# BOTCPCB_IXYS.net
KiCad netlist of a schematic drawn in EAGLE
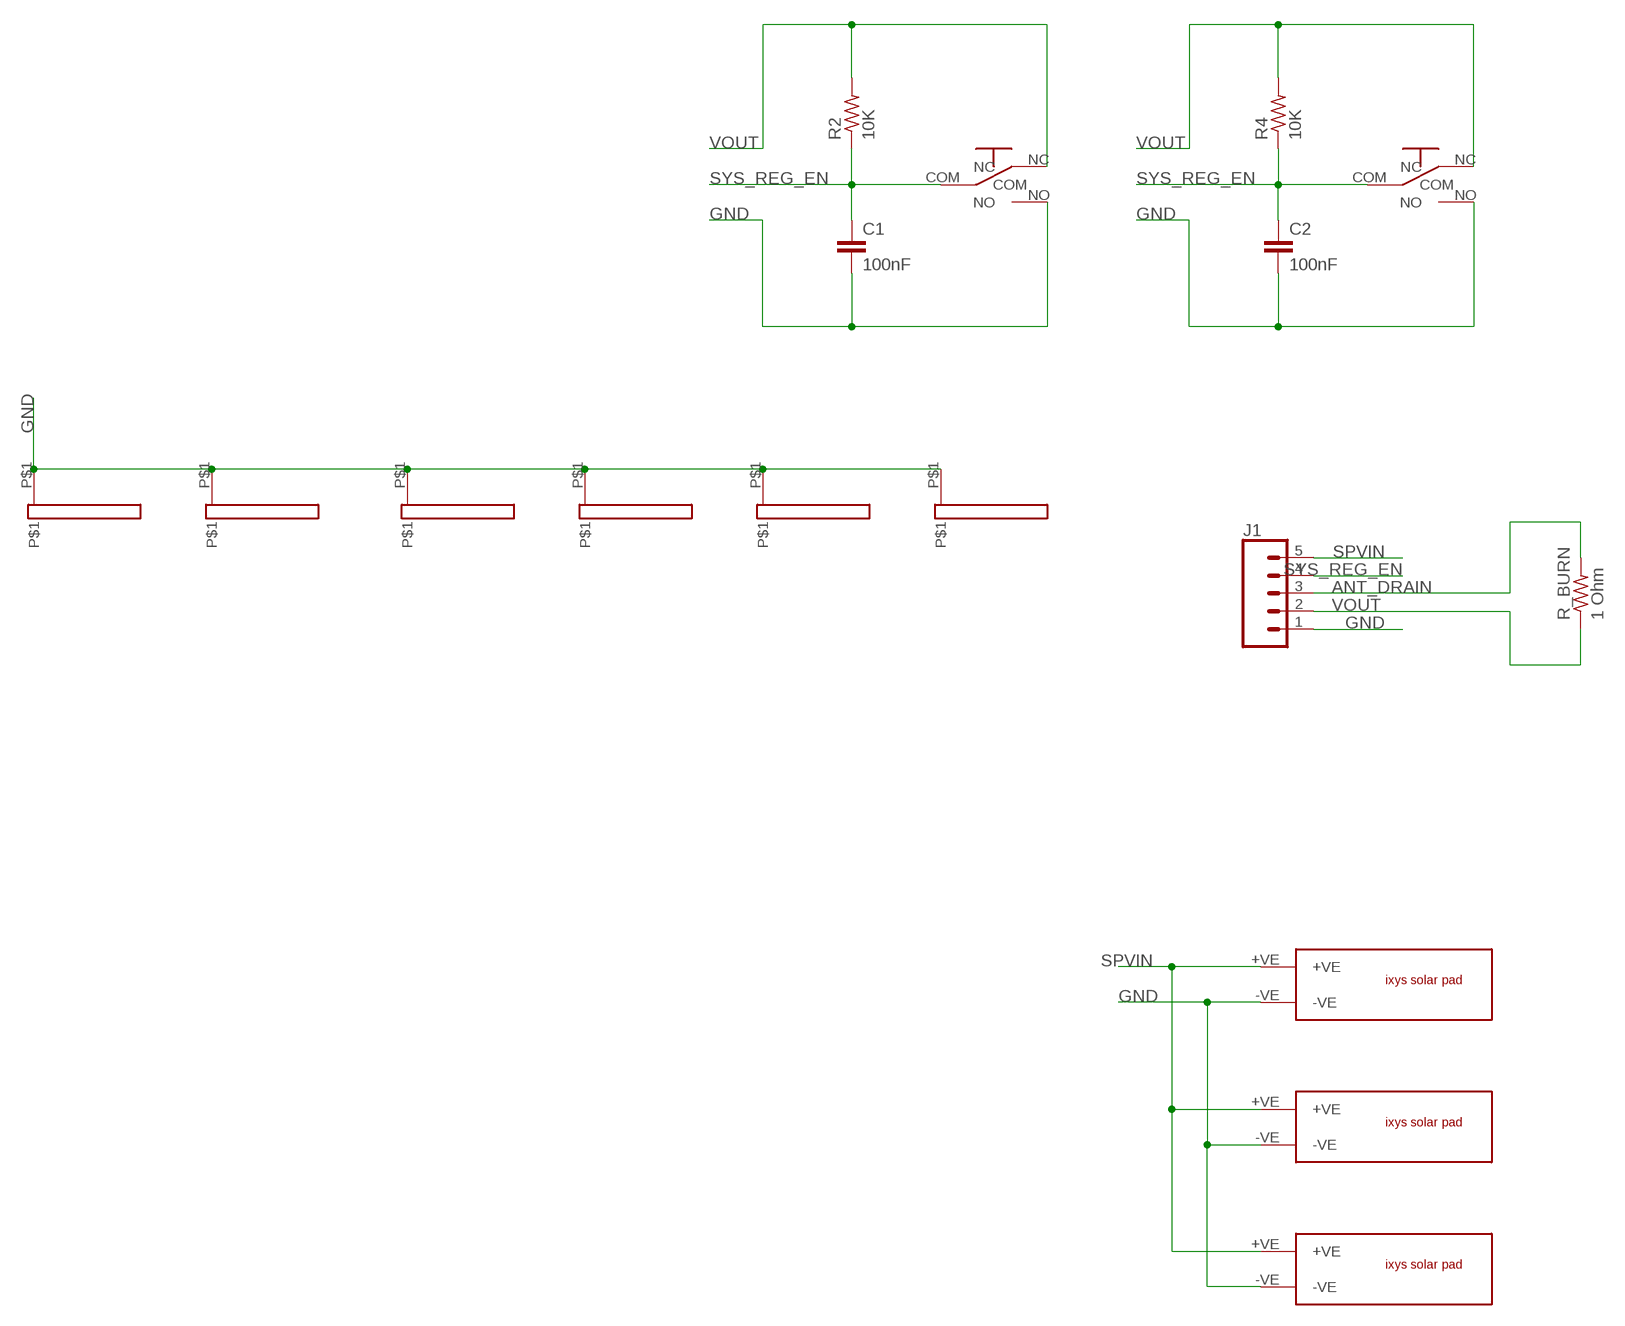
[diagram p0: schematic, sheet 1]

(export (version "E")
  (design (tool "Eeschema 10.0.6"))
  (components
    (comp (ref "C1")
      (value "100nF")
      (footprint "eagle-import:C025-024X044")
      (libsource (lib "eagle-import") (part "C-EU025-024X044"))
    )
    (comp (ref "C2")
      (value "100nF")
      (footprint "eagle-import:C025-024X044")
      (libsource (lib "eagle-import") (part "C-EU025-024X044"))
    )
    (comp (ref "J1")
      (value "CONN_05NO_SILK")
      (footprint "eagle-import:1X05_NO_SILK")
      (libsource (lib "eagle-import") (part "CONN_05NO_SILK"))
    )
    (comp (ref "R2")
      (value "10K")
      (footprint "eagle-import:0204_5")
      (libsource (lib "eagle-import") (part "R-US_0204/5"))
    )
    (comp (ref "R4")
      (value "10K")
      (footprint "eagle-import:0204_5")
      (libsource (lib "eagle-import") (part "R-US_0204/5"))
    )
    (comp (ref "R_BURN")
      (value "1 Ohm")
      (footprint "eagle-import:0204_5")
      (libsource (lib "eagle-import") (part "R-US_0204/5"))
    )
    (comp (ref "U$1")
      (value "16X2")
      (footprint "eagle-import:16X2")
      (libsource (lib "eagle-import") (part "16X2"))
    )
    (comp (ref "U$2")
      (value "16X2")
      (footprint "eagle-import:16X2")
      (libsource (lib "eagle-import") (part "16X2"))
    )
    (comp (ref "U$3")
      (value "OMRON-D2FA")
      (footprint "eagle-import:OMRON-D2F-A")
      (libsource (lib "eagle-import") (part "OMRON-D2FA"))
    )
    (comp (ref "U$4")
      (value "16X2")
      (footprint "eagle-import:16X2")
      (libsource (lib "eagle-import") (part "16X2"))
    )
    (comp (ref "U$5")
      (value "16X2")
      (footprint "eagle-import:16X2")
      (libsource (lib "eagle-import") (part "16X2"))
    )
    (comp (ref "U$6")
      (value "OMRON-D2FA")
      (footprint "eagle-import:OMRON-D2F-A")
      (libsource (lib "eagle-import") (part "OMRON-D2FA"))
    )
    (comp (ref "U$7")
      (value "16X2")
      (footprint "eagle-import:16X2")
      (libsource (lib "eagle-import") (part "16X2"))
    )
    (comp (ref "U$8")
      (value "16X2")
      (footprint "eagle-import:16X2")
      (libsource (lib "eagle-import") (part "16X2"))
    )
    (comp (ref "U$9")
      (value "IXYS")
      (footprint "eagle-import:IXYS")
      (libsource (lib "eagle-import") (part "IXYS"))
    )
    (comp (ref "U$11")
      (value "IXYS")
      (footprint "eagle-import:IXYS")
      (libsource (lib "eagle-import") (part "IXYS"))
    )
    (comp (ref "U$12")
      (value "IXYS")
      (footprint "eagle-import:IXYS")
      (libsource (lib "eagle-import") (part "IXYS"))
    )
  )
  (nets
    (net (code "1") (name "/ANT_DRAIN") (class "Default")
      (node (ref "J1") (pin "3") (pinfunction "3_3") (pintype "passive"))
      (node (ref "R_BURN") (pin "2") (pinfunction "2_2") (pintype "passive"))
    )
    (net (code "2") (name "/GND") (class "Default")
      (node (ref "C1") (pin "2") (pinfunction "2_2") (pintype "passive"))
      (node (ref "C2") (pin "2") (pinfunction "2_2") (pintype "passive"))
      (node (ref "J1") (pin "1") (pinfunction "1_1") (pintype "passive"))
      (node (ref "U$1") (pin "P$1") (pinfunction "P$1_P$1") (pintype "bidirectional"))
      (node (ref "U$11") (pin "-VE") (pinfunction "-VE_-VE") (pintype "bidirectional"))
      (node (ref "U$12") (pin "-VE") (pinfunction "-VE_-VE") (pintype "bidirectional"))
      (node (ref "U$2") (pin "P$1") (pinfunction "P$1_P$1") (pintype "bidirectional"))
      (node (ref "U$3") (pin "NO") (pinfunction "NO_NO") (pintype "bidirectional"))
      (node (ref "U$4") (pin "P$1") (pinfunction "P$1_P$1") (pintype "bidirectional"))
      (node (ref "U$5") (pin "P$1") (pinfunction "P$1_P$1") (pintype "bidirectional"))
      (node (ref "U$6") (pin "NO") (pinfunction "NO_NO") (pintype "bidirectional"))
      (node (ref "U$7") (pin "P$1") (pinfunction "P$1_P$1") (pintype "bidirectional"))
      (node (ref "U$8") (pin "P$1") (pinfunction "P$1_P$1") (pintype "bidirectional"))
      (node (ref "U$9") (pin "-VE") (pinfunction "-VE_-VE") (pintype "bidirectional"))
    )
    (net (code "3") (name "/SPVIN") (class "Default")
      (node (ref "J1") (pin "5") (pinfunction "5_5") (pintype "passive"))
      (node (ref "U$11") (pin "+VE") (pinfunction "+VE_+VE") (pintype "bidirectional"))
      (node (ref "U$12") (pin "+VE") (pinfunction "+VE_+VE") (pintype "bidirectional"))
      (node (ref "U$9") (pin "+VE") (pinfunction "+VE_+VE") (pintype "bidirectional"))
    )
    (net (code "4") (name "/SYS_REG_EN") (class "Default")
      (node (ref "C1") (pin "1") (pinfunction "1_1") (pintype "passive"))
      (node (ref "C2") (pin "1") (pinfunction "1_1") (pintype "passive"))
      (node (ref "J1") (pin "4") (pinfunction "4_4") (pintype "passive"))
      (node (ref "R2") (pin "1") (pinfunction "1_1") (pintype "passive"))
      (node (ref "R4") (pin "1") (pinfunction "1_1") (pintype "passive"))
      (node (ref "U$3") (pin "COM") (pinfunction "COM_COM") (pintype "bidirectional"))
      (node (ref "U$6") (pin "COM") (pinfunction "COM_COM") (pintype "bidirectional"))
    )
    (net (code "5") (name "/VOUT") (class "Default")
      (node (ref "J1") (pin "2") (pinfunction "2_2") (pintype "passive"))
      (node (ref "R2") (pin "2") (pinfunction "2_2") (pintype "passive"))
      (node (ref "R4") (pin "2") (pinfunction "2_2") (pintype "passive"))
      (node (ref "R_BURN") (pin "1") (pinfunction "1_1") (pintype "passive"))
      (node (ref "U$3") (pin "NC") (pinfunction "NC_NC") (pintype "bidirectional"))
      (node (ref "U$6") (pin "NC") (pinfunction "NC_NC") (pintype "bidirectional"))
    )
  )
)
